# SquareCount.net
KiCad netlist of a schematic drawn in EAGLE
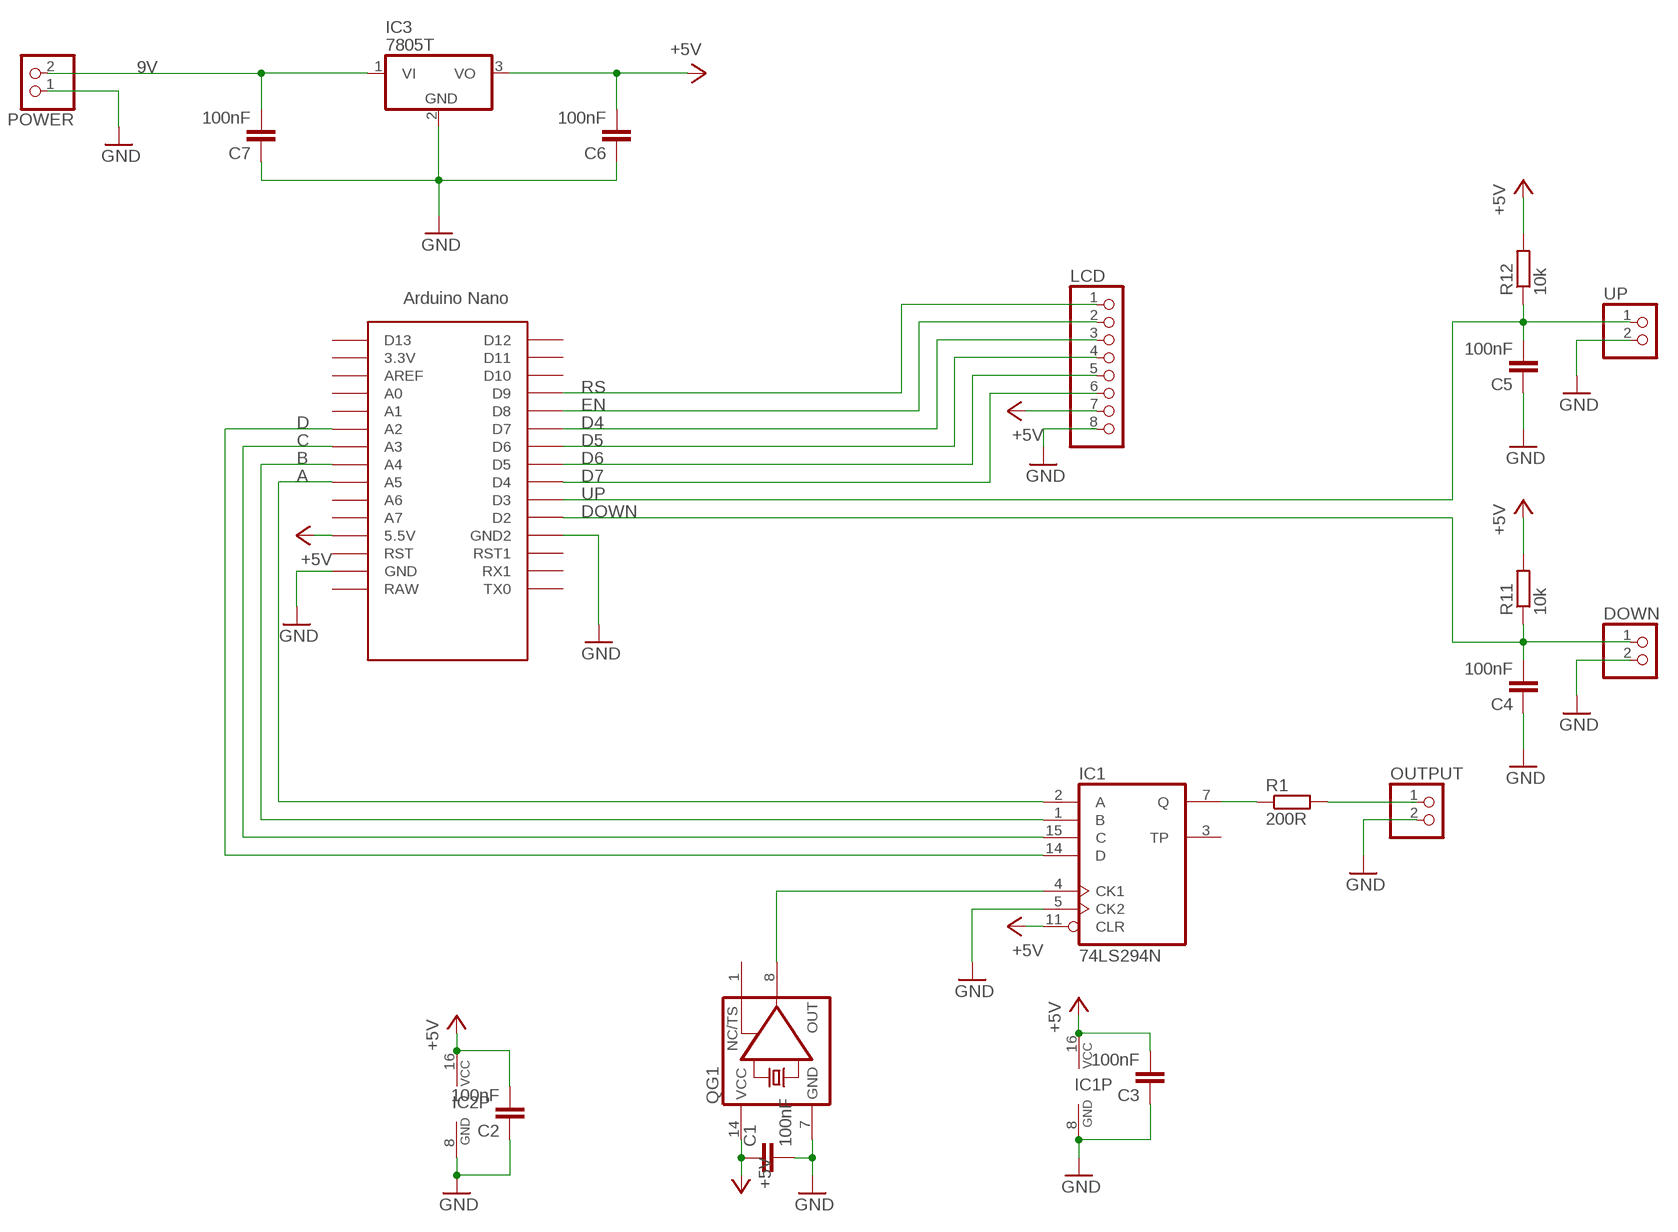
[diagram p0: schematic, sheet 1]

(export (version "E")
  (design (tool "Eeschema 10.0.6"))
  (components
    (comp (ref "C1")
      (value "100nF")
      (footprint "eagle-import:C0805")
      (libsource (lib "eagle-import") (part "C-EUC0805"))
    )
    (comp (ref "C2")
      (value "100nF")
      (footprint "eagle-import:C0805")
      (libsource (lib "eagle-import") (part "C-EUC0805"))
    )
    (comp (ref "C3")
      (value "100nF")
      (footprint "eagle-import:C0805")
      (libsource (lib "eagle-import") (part "C-EUC0805"))
    )
    (comp (ref "C4")
      (value "100nF")
      (footprint "eagle-import:C0805")
      (libsource (lib "eagle-import") (part "C-EUC0805"))
    )
    (comp (ref "C5")
      (value "100nF")
      (footprint "eagle-import:C0805")
      (libsource (lib "eagle-import") (part "C-EUC0805"))
    )
    (comp (ref "C6")
      (value "100nF")
      (footprint "eagle-import:C0805")
      (libsource (lib "eagle-import") (part "C-EUC0805"))
    )
    (comp (ref "C7")
      (value "100nF")
      (footprint "eagle-import:C0805")
      (libsource (lib "eagle-import") (part "C-EUC0805"))
    )
    (comp (ref "DOWN")
      (value "PINHD-1X2")
      (footprint "eagle-import:1X02")
      (libsource (lib "eagle-import") (part "PINHD-1X2"))
    )
    (comp (ref "IC1")
      (value "74LS294N")
      (footprint "eagle-import:DIL16")
      (libsource (lib "eagle-import") (part "74294NLS"))
    )
    (comp (ref "IC2")
      (value "74HC147N")
      (footprint "eagle-import:DIL16")
      (libsource (lib "eagle-import") (part "74147NHC"))
    )
    (comp (ref "IC3")
      (value "7805T")
      (footprint "eagle-import:TO220H")
      (libsource (lib "eagle-import") (part "78T05"))
    )
    (comp (ref "LCD")
      (value "PINHD-1X8")
      (footprint "eagle-import:1X08")
      (libsource (lib "eagle-import") (part "PINHD-1X8"))
    )
    (comp (ref "OUTPUT")
      (value "PINHD-1X2")
      (footprint "eagle-import:1X02")
      (libsource (lib "eagle-import") (part "PINHD-1X2"))
    )
    (comp (ref "POWER")
      (value "PINHD-1X2")
      (footprint "eagle-import:1X02")
      (libsource (lib "eagle-import") (part "PINHD-1X2"))
    )
    (comp (ref "QG1")
      (value "XO-14")
      (footprint "eagle-import:DIL14S")
      (libsource (lib "eagle-import") (part "XO-14"))
    )
    (comp (ref "R1")
      (value "200R")
      (footprint "eagle-import:M0805")
      (libsource (lib "eagle-import") (part "R-EU_M0805"))
    )
    (comp (ref "R11")
      (value "10k")
      (footprint "eagle-import:M0805")
      (libsource (lib "eagle-import") (part "R-EU_M0805"))
    )
    (comp (ref "R12")
      (value "10k")
      (footprint "eagle-import:M0805")
      (libsource (lib "eagle-import") (part "R-EU_M0805"))
    )
    (comp (ref "U$1")
      (value "NANO")
      (footprint "eagle-import:NANO")
      (libsource (lib "eagle-import") (part "NANO"))
    )
    (comp (ref "UP")
      (value "PINHD-1X2")
      (footprint "eagle-import:1X02")
      (libsource (lib "eagle-import") (part "PINHD-1X2"))
    )
  )
  (nets
    (net (code "1") (name "+5V") (class "Default")
      (node (ref "C1") (pin "1") (pinfunction "1_1") (pintype "passive"))
      (node (ref "C2") (pin "2") (pinfunction "2_2") (pintype "passive"))
      (node (ref "C3") (pin "2") (pinfunction "2_2") (pintype "passive"))
      (node (ref "C6") (pin "2") (pinfunction "2_2") (pintype "passive"))
      (node (ref "IC1") (pin "11") (pinfunction "CLR_11") (pintype "input"))
      (node (ref "IC1") (pin "16") (pinfunction "VCC_16") (pintype "power_in"))
      (node (ref "IC2") (pin "16") (pinfunction "VCC_16") (pintype "power_in"))
      (node (ref "IC3") (pin "3") (pinfunction "VO_3") (pintype "passive"))
      (node (ref "LCD") (pin "7") (pinfunction "7_7") (pintype "passive"))
      (node (ref "QG1") (pin "14") (pinfunction "VCC_14") (pintype "power_in"))
      (node (ref "R11") (pin "2") (pinfunction "2_2") (pintype "passive"))
      (node (ref "R12") (pin "2") (pinfunction "2_2") (pintype "passive"))
      (node (ref "U$1") (pin "5V") (pinfunction "5.5V_5V") (pintype "bidirectional"))
    )
    (net (code "2") (name "/9V") (class "Default")
      (node (ref "C7") (pin "2") (pinfunction "2_2") (pintype "passive"))
      (node (ref "IC3") (pin "1") (pinfunction "VI_1") (pintype "input"))
      (node (ref "POWER") (pin "2") (pinfunction "2_2") (pintype "passive"))
    )
    (net (code "3") (name "/A") (class "Default")
      (node (ref "IC1") (pin "2") (pinfunction "A_2") (pintype "input"))
      (node (ref "U$1") (pin "A5") (pinfunction "A5_A5") (pintype "bidirectional"))
    )
    (net (code "4") (name "/B") (class "Default")
      (node (ref "IC1") (pin "1") (pinfunction "B_1") (pintype "input"))
      (node (ref "U$1") (pin "A4") (pinfunction "A4_A4") (pintype "bidirectional"))
    )
    (net (code "5") (name "/C") (class "Default")
      (node (ref "IC1") (pin "15") (pinfunction "C_15") (pintype "input"))
      (node (ref "U$1") (pin "A3") (pinfunction "A3_A3") (pintype "bidirectional"))
    )
    (net (code "6") (name "/D") (class "Default")
      (node (ref "IC1") (pin "14") (pinfunction "D_14") (pintype "input"))
      (node (ref "U$1") (pin "A2") (pinfunction "A2_A2") (pintype "bidirectional"))
    )
    (net (code "7") (name "/D4") (class "Default")
      (node (ref "LCD") (pin "3") (pinfunction "3_3") (pintype "passive"))
      (node (ref "U$1") (pin "D7") (pinfunction "D7_D7") (pintype "bidirectional"))
    )
    (net (code "8") (name "/D5") (class "Default")
      (node (ref "LCD") (pin "4") (pinfunction "4_4") (pintype "passive"))
      (node (ref "U$1") (pin "D6") (pinfunction "D6_D6") (pintype "bidirectional"))
    )
    (net (code "9") (name "/D6") (class "Default")
      (node (ref "LCD") (pin "5") (pinfunction "5_5") (pintype "passive"))
      (node (ref "U$1") (pin "D5") (pinfunction "D5_D5") (pintype "bidirectional"))
    )
    (net (code "10") (name "/D7") (class "Default")
      (node (ref "LCD") (pin "6") (pinfunction "6_6") (pintype "passive"))
      (node (ref "U$1") (pin "D4") (pinfunction "D4_D4") (pintype "bidirectional"))
    )
    (net (code "11") (name "/DOWN") (class "Default")
      (node (ref "C4") (pin "2") (pinfunction "2_2") (pintype "passive"))
      (node (ref "DOWN") (pin "1") (pinfunction "1_1") (pintype "passive"))
      (node (ref "R11") (pin "1") (pinfunction "1_1") (pintype "passive"))
      (node (ref "U$1") (pin "D2") (pinfunction "D2_D2") (pintype "bidirectional"))
    )
    (net (code "12") (name "/EN") (class "Default")
      (node (ref "LCD") (pin "2") (pinfunction "2_2") (pintype "passive"))
      (node (ref "U$1") (pin "D8") (pinfunction "D8_D8") (pintype "bidirectional"))
    )
    (net (code "13") (name "/RS") (class "Default")
      (node (ref "LCD") (pin "1") (pinfunction "1_1") (pintype "passive"))
      (node (ref "U$1") (pin "D9") (pinfunction "D9_D9") (pintype "bidirectional"))
    )
    (net (code "14") (name "/UP") (class "Default")
      (node (ref "C5") (pin "2") (pinfunction "2_2") (pintype "passive"))
      (node (ref "R12") (pin "1") (pinfunction "1_1") (pintype "passive"))
      (node (ref "U$1") (pin "D3") (pinfunction "D3_D3") (pintype "bidirectional"))
      (node (ref "UP") (pin "1") (pinfunction "1_1") (pintype "passive"))
    )
    (net (code "15") (name "GND") (class "Default")
      (node (ref "C1") (pin "2") (pinfunction "2_2") (pintype "passive"))
      (node (ref "C2") (pin "1") (pinfunction "1_1") (pintype "passive"))
      (node (ref "C3") (pin "1") (pinfunction "1_1") (pintype "passive"))
      (node (ref "C4") (pin "1") (pinfunction "1_1") (pintype "passive"))
      (node (ref "C5") (pin "1") (pinfunction "1_1") (pintype "passive"))
      (node (ref "C6") (pin "1") (pinfunction "1_1") (pintype "passive"))
      (node (ref "C7") (pin "1") (pinfunction "1_1") (pintype "passive"))
      (node (ref "DOWN") (pin "2") (pinfunction "2_2") (pintype "passive"))
      (node (ref "IC1") (pin "5") (pinfunction "CK2_5") (pintype "input"))
      (node (ref "IC1") (pin "8") (pinfunction "GND_8") (pintype "power_in"))
      (node (ref "IC2") (pin "8") (pinfunction "GND_8") (pintype "power_in"))
      (node (ref "IC3") (pin "2") (pinfunction "GND_2") (pintype "passive"))
      (node (ref "LCD") (pin "8") (pinfunction "8_8") (pintype "passive"))
      (node (ref "OUTPUT") (pin "2") (pinfunction "2_2") (pintype "passive"))
      (node (ref "POWER") (pin "1") (pinfunction "1_1") (pintype "passive"))
      (node (ref "QG1") (pin "7") (pinfunction "GND_7") (pintype "power_in"))
      (node (ref "U$1") (pin "GND") (pinfunction "GND_GND") (pintype "bidirectional"))
      (node (ref "U$1") (pin "GND1") (pinfunction "GND2_GND1") (pintype "bidirectional"))
      (node (ref "UP") (pin "2") (pinfunction "2_2") (pintype "passive"))
    )
    (net (code "16") (name "Net-(IC1A-CK1)") (class "Default")
      (node (ref "IC1") (pin "4") (pinfunction "CK1_4") (pintype "input"))
      (node (ref "QG1") (pin "8") (pinfunction "OUT_8") (pintype "output"))
    )
    (net (code "17") (name "Net-(IC1A-Q)") (class "Default")
      (node (ref "IC1") (pin "7") (pinfunction "Q_7") (pintype "output"))
      (node (ref "R1") (pin "1") (pinfunction "1_1") (pintype "passive"))
    )
    (net (code "18") (name "Net-(OUTPUT-Pad1)") (class "Default")
      (node (ref "OUTPUT") (pin "1") (pinfunction "1_1") (pintype "passive"))
      (node (ref "R1") (pin "2") (pinfunction "2_2") (pintype "passive"))
    )
    (net (code "19") (name "unconnected-(IC1A-TP-Pad3)") (class "Default")
      (node (ref "IC1") (pin "3") (pinfunction "TP_3") (pintype "output"))
    )
    (net (code "20") (name "unconnected-(QG1-TS-Pad1)") (class "Default")
      (node (ref "QG1") (pin "1") (pinfunction "TS_1") (pintype "passive"))
    )
    (net (code "21") (name "unconnected-(U$1-Pad3.3V)") (class "Default")
      (node (ref "U$1") (pin "3.3V") (pinfunction "3.3V_3.3V") (pintype "bidirectional"))
    )
    (net (code "22") (name "unconnected-(U$1-PadA0)") (class "Default")
      (node (ref "U$1") (pin "A0") (pinfunction "A0_A0") (pintype "bidirectional"))
    )
    (net (code "23") (name "unconnected-(U$1-PadA1)") (class "Default")
      (node (ref "U$1") (pin "A1") (pinfunction "A1_A1") (pintype "bidirectional"))
    )
    (net (code "24") (name "unconnected-(U$1-PadA6)") (class "Default")
      (node (ref "U$1") (pin "A6") (pinfunction "A6_A6") (pintype "bidirectional"))
    )
    (net (code "25") (name "unconnected-(U$1-PadA7)") (class "Default")
      (node (ref "U$1") (pin "A7") (pinfunction "A7_A7") (pintype "bidirectional"))
    )
    (net (code "26") (name "unconnected-(U$1-PadAREF)") (class "Default")
      (node (ref "U$1") (pin "AREF") (pinfunction "AREF_AREF") (pintype "bidirectional"))
    )
    (net (code "27") (name "unconnected-(U$1-PadD10)") (class "Default")
      (node (ref "U$1") (pin "D10") (pinfunction "D10_D10") (pintype "bidirectional"))
    )
    (net (code "28") (name "unconnected-(U$1-PadD11)") (class "Default")
      (node (ref "U$1") (pin "D11") (pinfunction "D11_D11") (pintype "bidirectional"))
    )
    (net (code "29") (name "unconnected-(U$1-PadD12)") (class "Default")
      (node (ref "U$1") (pin "D12") (pinfunction "D12_D12") (pintype "bidirectional"))
    )
    (net (code "30") (name "unconnected-(U$1-PadD13)") (class "Default")
      (node (ref "U$1") (pin "D13") (pinfunction "D13_D13") (pintype "bidirectional"))
    )
    (net (code "31") (name "unconnected-(U$1-PadICSP1)") (class "Default")
      (node (ref "U$1") (pin "ICSP1") (pinfunction "ICSP1_ICSP1") (pintype "bidirectional"))
    )
    (net (code "32") (name "unconnected-(U$1-PadICSP2)") (class "Default")
      (node (ref "U$1") (pin "ICSP2") (pinfunction "ICSP2_ICSP2") (pintype "bidirectional"))
    )
    (net (code "33") (name "unconnected-(U$1-PadICSP3)") (class "Default")
      (node (ref "U$1") (pin "ICSP3") (pinfunction "ICSP3_ICSP3") (pintype "bidirectional"))
    )
    (net (code "34") (name "unconnected-(U$1-PadICSP4)") (class "Default")
      (node (ref "U$1") (pin "ICSP4") (pinfunction "ICSP4_ICSP4") (pintype "bidirectional"))
    )
    (net (code "35") (name "unconnected-(U$1-PadICSP5)") (class "Default")
      (node (ref "U$1") (pin "ICSP5") (pinfunction "ICSP5_ICSP5") (pintype "bidirectional"))
    )
    (net (code "36") (name "unconnected-(U$1-PadICSP6)") (class "Default")
      (node (ref "U$1") (pin "ICSP6") (pinfunction "ICSP6_ICSP6") (pintype "bidirectional"))
    )
    (net (code "37") (name "unconnected-(U$1-PadRAW)") (class "Default")
      (node (ref "U$1") (pin "RAW") (pinfunction "RAW_RAW") (pintype "bidirectional"))
    )
    (net (code "38") (name "unconnected-(U$1-PadRST)") (class "Default")
      (node (ref "U$1") (pin "RST") (pinfunction "RST_RST") (pintype "bidirectional"))
    )
    (net (code "39") (name "unconnected-(U$1-PadRST1)") (class "Default")
      (node (ref "U$1") (pin "RST1") (pinfunction "RST1_RST1") (pintype "bidirectional"))
    )
    (net (code "40") (name "unconnected-(U$1-PadRX1)") (class "Default")
      (node (ref "U$1") (pin "RX1") (pinfunction "RX1_RX1") (pintype "bidirectional"))
    )
    (net (code "41") (name "unconnected-(U$1-PadTX0)") (class "Default")
      (node (ref "U$1") (pin "TX0") (pinfunction "TX0_TX0") (pintype "bidirectional"))
    )
  )
)
